# schematic.net
KiCad netlist of a schematic drawn in EAGLE
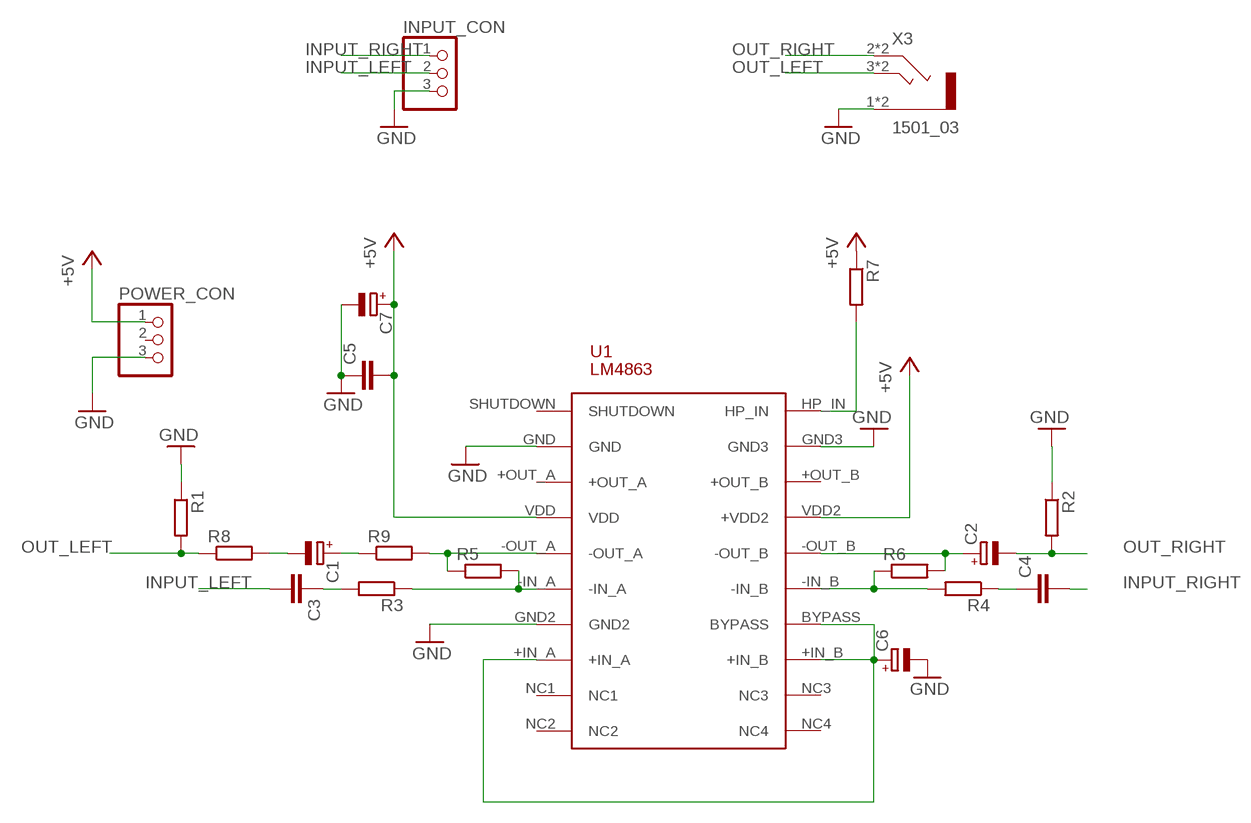
[diagram p0: schematic, sheet 1]

(export (version "E")
  (design (tool "Eeschema 10.0.6"))
  (components
    (comp (ref "C1")
      (value "CPOL-EUE2.5-7")
      (footprint "eagle-import:E2,5-7")
      (libsource (lib "eagle-import") (part "CPOL-EUE2.5-7"))
    )
    (comp (ref "C2")
      (value "CPOL-EUE2.5-7")
      (footprint "eagle-import:E2,5-7")
      (libsource (lib "eagle-import") (part "CPOL-EUE2.5-7"))
    )
    (comp (ref "C3")
      (value "C-EU050-035X075")
      (footprint "eagle-import:C050-035X075")
      (libsource (lib "eagle-import") (part "C-EU050-035X075"))
    )
    (comp (ref "C4")
      (value "C-EU050-035X075")
      (footprint "eagle-import:C050-035X075")
      (libsource (lib "eagle-import") (part "C-EU050-035X075"))
    )
    (comp (ref "C5")
      (value "C-EU050-024X044")
      (footprint "eagle-import:C050-024X044")
      (libsource (lib "eagle-import") (part "C-EU050-024X044"))
    )
    (comp (ref "C6")
      (value "CPOL-EUE2.5-7")
      (footprint "eagle-import:E2,5-7")
      (libsource (lib "eagle-import") (part "resistor_CPOL-EUE2.5-7"))
    )
    (comp (ref "C7")
      (value "CPOL-EUE2.5-7")
      (footprint "eagle-import:E2,5-7")
      (libsource (lib "eagle-import") (part "CPOL-EUE2.5-7"))
    )
    (comp (ref "INPUT_CON")
      (value "PINHD-1X3CB")
      (footprint "eagle-import:1X03-CLEANBIG")
      (libsource (lib "eagle-import") (part "PINHD-1X3CB"))
    )
    (comp (ref "POWER_CON")
      (value "PINHD-1X3")
      (footprint "eagle-import:1X03")
      (libsource (lib "eagle-import") (part "PINHD-1X3"))
    )
    (comp (ref "R1")
      (value "R-EU_0207/2V")
      (footprint "eagle-import:0207_2V")
      (libsource (lib "eagle-import") (part "R-EU_0207/2V"))
    )
    (comp (ref "R2")
      (value "R-EU_0207/10")
      (footprint "eagle-import:0207_10")
      (libsource (lib "eagle-import") (part "R-EU_0207/10"))
    )
    (comp (ref "R3")
      (value "R-EU_0207/10")
      (footprint "eagle-import:0207_10")
      (libsource (lib "eagle-import") (part "R-EU_0207/10"))
    )
    (comp (ref "R4")
      (value "R-EU_0207/2V")
      (footprint "eagle-import:0207_2V")
      (libsource (lib "eagle-import") (part "R-EU_0207/2V"))
    )
    (comp (ref "R5")
      (value "R-EU_0204/2V")
      (footprint "eagle-import:0204V")
      (libsource (lib "eagle-import") (part "R-EU_0204/2V"))
    )
    (comp (ref "R6")
      (value "R-EU_0207/2V")
      (footprint "eagle-import:0207_2V")
      (libsource (lib "eagle-import") (part "R-EU_0207/2V"))
    )
    (comp (ref "R7")
      (value "R-EU_0207/10")
      (footprint "eagle-import:0207_10")
      (libsource (lib "eagle-import") (part "R-EU_0207/10"))
    )
    (comp (ref "R8")
      (value "R-EU_0204/7")
      (footprint "eagle-import:0204_7")
      (libsource (lib "eagle-import") (part "R-EU_0204/7"))
    )
    (comp (ref "R9")
      (value "R-EU_0204/7")
      (footprint "eagle-import:0204_7")
      (libsource (lib "eagle-import") (part "R-EU_0204/7"))
    )
    (comp (ref "U1")
      (value "LM4863")
      (footprint "eagle-import:TSSOP20")
      (libsource (lib "eagle-import") (part "LM4863"))
    )
    (comp (ref "X3")
      (value "1501_03")
      (footprint "eagle-import:1501_03")
      (libsource (lib "eagle-import") (part "1501_03"))
    )
  )
  (nets
    (net (code "1") (name "+5V") (class "Default")
      (node (ref "C5") (pin "2") (pinfunction "2_2") (pintype "passive"))
      (node (ref "C7") (pin "+") (pinfunction "+_+") (pintype "passive"))
      (node (ref "POWER_CON") (pin "1") (pinfunction "1_1") (pintype "passive"))
      (node (ref "R7") (pin "1") (pinfunction "1_1") (pintype "passive"))
      (node (ref "U1") (pin "VDD") (pinfunction "VDD_VDD") (pintype "power_in"))
      (node (ref "U1") (pin "VDD2") (pinfunction "+VDD2_VDD2") (pintype "power_in"))
    )
    (net (code "2") (name "/INPUT_LEFT") (class "Default")
      (node (ref "C3") (pin "2") (pinfunction "2_2") (pintype "passive"))
      (node (ref "INPUT_CON") (pin "2") (pinfunction "2_2") (pintype "passive"))
    )
    (net (code "3") (name "/INPUT_RIGHT") (class "Default")
      (node (ref "C4") (pin "2") (pinfunction "2_2") (pintype "passive"))
      (node (ref "INPUT_CON") (pin "1") (pinfunction "1_1") (pintype "passive"))
    )
    (net (code "4") (name "/OUT_LEFT") (class "Default")
      (node (ref "R1") (pin "2") (pinfunction "2_2") (pintype "passive"))
      (node (ref "R8") (pin "1") (pinfunction "1_1") (pintype "passive"))
      (node (ref "X3") (pin "3") (pinfunction "3_3") (pintype "passive"))
      (node (ref "X3") (pin "33") (pinfunction "3_33") (pintype "passive"))
    )
    (net (code "5") (name "/OUT_RIGHT") (class "Default")
      (node (ref "C2") (pin "-") (pinfunction "-_-") (pintype "passive"))
      (node (ref "R2") (pin "2") (pinfunction "2_2") (pintype "passive"))
      (node (ref "X3") (pin "2") (pinfunction "2_2") (pintype "passive"))
      (node (ref "X3") (pin "22") (pinfunction "2_22") (pintype "passive"))
    )
    (net (code "6") (name "GND") (class "Default")
      (node (ref "C5") (pin "1") (pinfunction "1_1") (pintype "passive"))
      (node (ref "C6") (pin "-") (pinfunction "-_-") (pintype "passive"))
      (node (ref "C7") (pin "-") (pinfunction "-_-") (pintype "passive"))
      (node (ref "INPUT_CON") (pin "3") (pinfunction "3_3") (pintype "passive"))
      (node (ref "POWER_CON") (pin "3") (pinfunction "3_3") (pintype "passive"))
      (node (ref "R1") (pin "1") (pinfunction "1_1") (pintype "passive"))
      (node (ref "R2") (pin "1") (pinfunction "1_1") (pintype "passive"))
      (node (ref "U1") (pin "GND") (pinfunction "GND_GND") (pintype "power_in"))
      (node (ref "U1") (pin "GND2") (pinfunction "GND2_GND2") (pintype "bidirectional"))
      (node (ref "U1") (pin "GND3") (pinfunction "GND3_GND3") (pintype "power_in"))
      (node (ref "X3") (pin "1") (pinfunction "1_1") (pintype "passive"))
      (node (ref "X3") (pin "11") (pinfunction "1_11") (pintype "passive"))
    )
    (net (code "7") (name "Net-(C1-Pad+)") (class "Default")
      (node (ref "C1") (pin "+") (pinfunction "+_+") (pintype "passive"))
      (node (ref "R9") (pin "1") (pinfunction "1_1") (pintype "passive"))
    )
    (net (code "8") (name "Net-(C1-Pad-)") (class "Default")
      (node (ref "C1") (pin "-") (pinfunction "-_-") (pintype "passive"))
      (node (ref "R8") (pin "2") (pinfunction "2_2") (pintype "passive"))
    )
    (net (code "9") (name "Net-(C2-Pad+)") (class "Default")
      (node (ref "C2") (pin "+") (pinfunction "+_+") (pintype "passive"))
      (node (ref "R6") (pin "2") (pinfunction "2_2") (pintype "passive"))
      (node (ref "U1") (pin "-OUT_B") (pinfunction "-OUT_B_-OUT_B") (pintype "output"))
    )
    (net (code "10") (name "Net-(C3-Pad1)") (class "Default")
      (node (ref "C3") (pin "1") (pinfunction "1_1") (pintype "passive"))
      (node (ref "R3") (pin "2") (pinfunction "2_2") (pintype "passive"))
    )
    (net (code "11") (name "Net-(C4-Pad1)") (class "Default")
      (node (ref "C4") (pin "1") (pinfunction "1_1") (pintype "passive"))
      (node (ref "R4") (pin "1") (pinfunction "1_1") (pintype "passive"))
    )
    (net (code "12") (name "Net-(C6-Pad+)") (class "Default")
      (node (ref "C6") (pin "+") (pinfunction "+_+") (pintype "passive"))
      (node (ref "U1") (pin "+IN_A") (pinfunction "+IN_A_+IN_A") (pintype "input"))
      (node (ref "U1") (pin "+IN_B") (pinfunction "+IN_B_+IN_B") (pintype "input"))
      (node (ref "U1") (pin "BYPASS") (pinfunction "BYPASS_BYPASS") (pintype "passive"))
    )
    (net (code "13") (name "Net-(R3-Pad1)") (class "Default")
      (node (ref "R3") (pin "1") (pinfunction "1_1") (pintype "passive"))
      (node (ref "R5") (pin "2") (pinfunction "2_2") (pintype "passive"))
      (node (ref "U1") (pin "-IN_A") (pinfunction "-IN_A_-IN_A") (pintype "input"))
    )
    (net (code "14") (name "Net-(R4-Pad2)") (class "Default")
      (node (ref "R4") (pin "2") (pinfunction "2_2") (pintype "passive"))
      (node (ref "R6") (pin "1") (pinfunction "1_1") (pintype "passive"))
      (node (ref "U1") (pin "-IN_B") (pinfunction "-IN_B_-IN_B") (pintype "bidirectional"))
    )
    (net (code "15") (name "Net-(R5-Pad1)") (class "Default")
      (node (ref "R5") (pin "1") (pinfunction "1_1") (pintype "passive"))
      (node (ref "R9") (pin "2") (pinfunction "2_2") (pintype "passive"))
      (node (ref "U1") (pin "-OUT_A") (pinfunction "-OUT_A_-OUT_A") (pintype "output"))
    )
    (net (code "16") (name "Net-(R7-Pad2)") (class "Default")
      (node (ref "R7") (pin "2") (pinfunction "2_2") (pintype "passive"))
      (node (ref "U1") (pin "HP_IN") (pinfunction "HP_IN_HP_IN") (pintype "input"))
    )
    (net (code "17") (name "unconnected-(POWER_CON-Pad2)") (class "Default")
      (node (ref "POWER_CON") (pin "2") (pinfunction "2_2") (pintype "passive"))
    )
    (net (code "18") (name "unconnected-(U1-Pad+OUT_A)") (class "Default")
      (node (ref "U1") (pin "+OUT_A") (pinfunction "+OUT_A_+OUT_A") (pintype "output"))
    )
    (net (code "19") (name "unconnected-(U1-Pad+OUT_B)") (class "Default")
      (node (ref "U1") (pin "+OUT_B") (pinfunction "+OUT_B_+OUT_B") (pintype "output"))
    )
    (net (code "20") (name "unconnected-(U1-PadNC1)") (class "Default")
      (node (ref "U1") (pin "NC1") (pinfunction "NC1_NC1") (pintype "no_connect"))
    )
    (net (code "21") (name "unconnected-(U1-PadNC2)") (class "Default")
      (node (ref "U1") (pin "NC2") (pinfunction "NC2_NC2") (pintype "no_connect"))
    )
    (net (code "22") (name "unconnected-(U1-PadNC3)") (class "Default")
      (node (ref "U1") (pin "NC3") (pinfunction "NC3_NC3") (pintype "no_connect"))
    )
    (net (code "23") (name "unconnected-(U1-PadNC4)") (class "Default")
      (node (ref "U1") (pin "NC4") (pinfunction "NC4_NC4") (pintype "no_connect"))
    )
    (net (code "24") (name "unconnected-(U1-PadSHUTDOWN)") (class "Default")
      (node (ref "U1") (pin "SHUTDOWN") (pinfunction "SHUTDOWN_SHUTDOWN") (pintype "input"))
    )
  )
)
